# MCU.net
KiCad netlist of a schematic drawn in Altium Designer
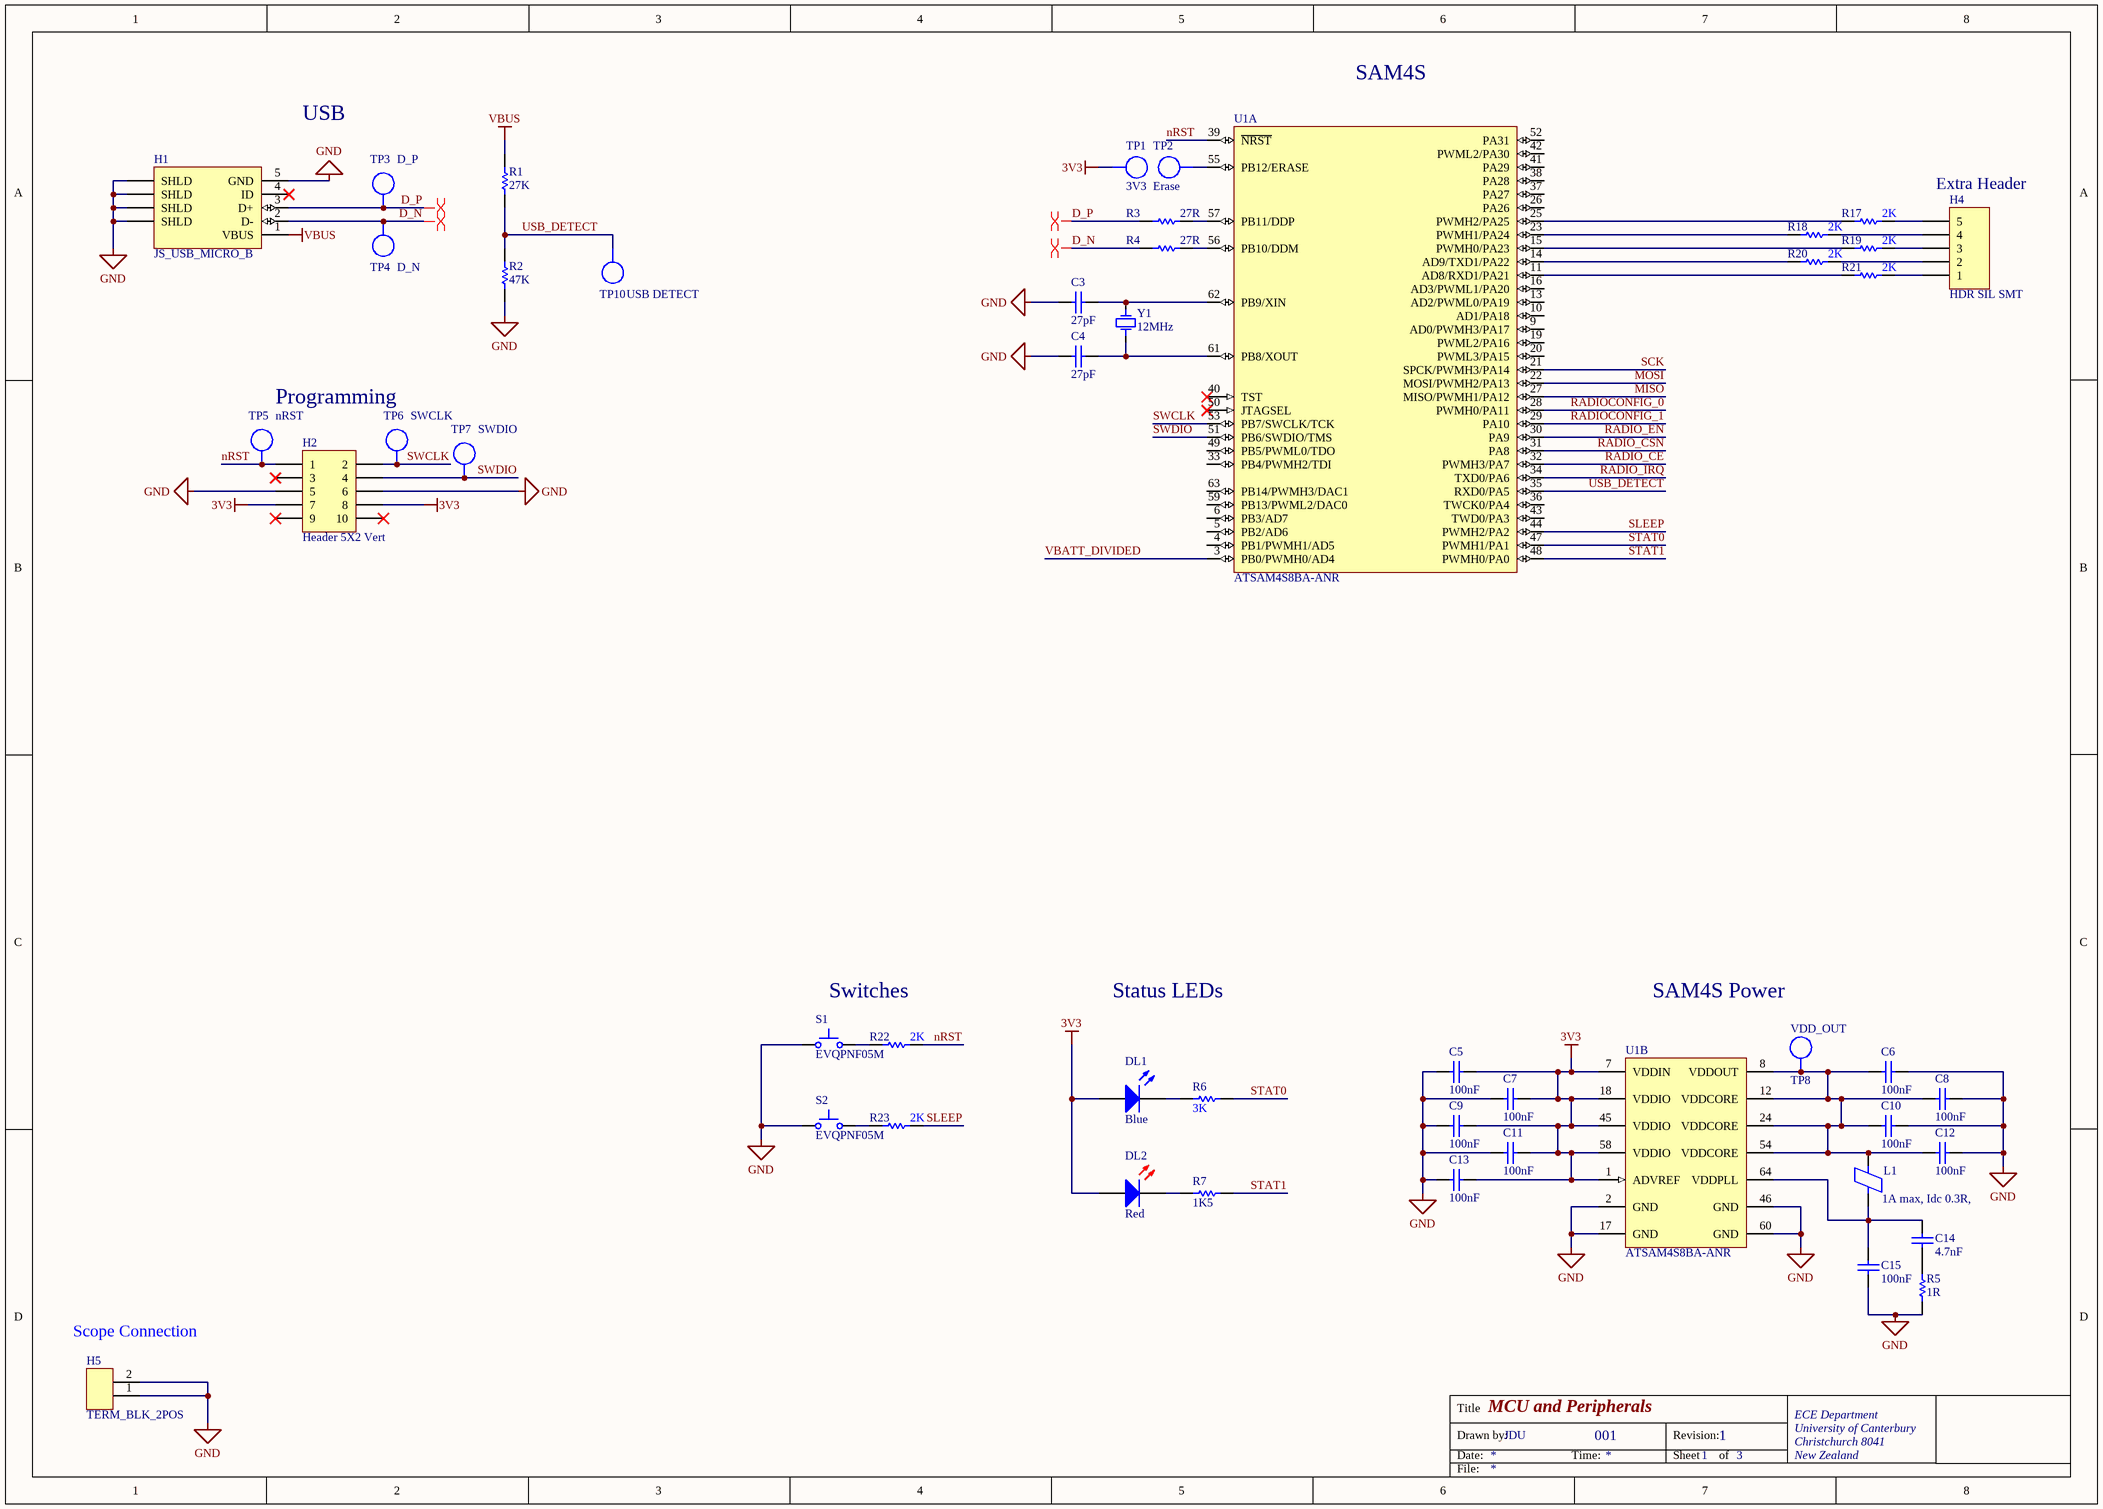
[diagram p0: MCU.SchDoc]

(export (version "E")
  (design (tool "Eeschema 10.0.6"))
  (components
    (comp (ref "C3")
      (value "27pF")
      (footprint "CAPC1608L")
      (description "CAP CER 27pF NPO/COG +-5% 50V 0603")
      (libsource (lib "ECE_ComponentsAD23") (part "CC_27pF_0603"))
    )
    (comp (ref "C4")
      (value "27pF")
      (footprint "CAPC1608L")
      (description "CAP CER 27pF NPO/COG +-5% 50V 0603")
      (libsource (lib "ECE_ComponentsAD23") (part "CC_27pF_0603"))
    )
    (comp (ref "C5")
      (value "100nF")
      (footprint "CAPC1608L")
      (description "CAP CER 100nF X7R +-10% 50V 0603")
      (libsource (lib "ECE_ComponentsAD23") (part "CC_100nF_0603"))
    )
    (comp (ref "C6")
      (value "100nF")
      (footprint "CAPC1608L")
      (description "CAP CER 100nF X7R +-10% 50V 0603")
      (libsource (lib "ECE_ComponentsAD23") (part "CC_100nF_0603"))
    )
    (comp (ref "C7")
      (value "100nF")
      (footprint "CAPC1608L")
      (description "CAP CER 100nF X7R +-10% 50V 0603")
      (libsource (lib "ECE_ComponentsAD23") (part "CC_100nF_0603"))
    )
    (comp (ref "C8")
      (value "100nF")
      (footprint "CAPC1608L")
      (description "CAP CER 100nF X7R +-10% 50V 0603")
      (libsource (lib "ECE_ComponentsAD23") (part "CC_100nF_0603"))
    )
    (comp (ref "C9")
      (value "100nF")
      (footprint "CAPC1608L")
      (description "CAP CER 100nF X7R +-10% 50V 0603")
      (libsource (lib "ECE_ComponentsAD23") (part "CC_100nF_0603"))
    )
    (comp (ref "C10")
      (value "100nF")
      (footprint "CAPC1608L")
      (description "CAP CER 100nF X7R +-10% 50V 0603")
      (libsource (lib "ECE_ComponentsAD23") (part "CC_100nF_0603"))
    )
    (comp (ref "C11")
      (value "100nF")
      (footprint "CAPC1608L")
      (description "CAP CER 100nF X7R +-10% 50V 0603")
      (libsource (lib "ECE_ComponentsAD23") (part "CC_100nF_0603"))
    )
    (comp (ref "C12")
      (value "100nF")
      (footprint "CAPC1608L")
      (description "CAP CER 100nF X7R +-10% 50V 0603")
      (libsource (lib "ECE_ComponentsAD23") (part "CC_100nF_0603"))
    )
    (comp (ref "C13")
      (value "100nF")
      (footprint "CAPC1608L")
      (description "CAP CER 100nF X7R +-10% 50V 0603")
      (libsource (lib "ECE_ComponentsAD23") (part "CC_100nF_0603"))
    )
    (comp (ref "C14")
      (value "4.7nF")
      (footprint "CAPC1608L")
      (description "CAP CER 4.7nF X7R +-10% 50V 0603")
      (libsource (lib "ECE_ComponentsAD23") (part "CC_4.7nF_0603"))
    )
    (comp (ref "C15")
      (value "100nF")
      (footprint "CAPC1608L")
      (description "CAP CER 100nF X7R +-10% 50V 0603")
      (libsource (lib "ECE_ComponentsAD23") (part "CC_100nF_0603"))
    )
    (comp (ref "DL1")
      (value "Blue")
      (footprint "WL-SMCW0603")
      (description "LED Blue 270mcd 0603 SMD")
      (fields
        (field (name "MANUFACTURER") "WURTH ELEKTRONIK")
        (field (name "MANUFACTURER PART NUMBER") "150060BS75000")
        (field (name "LED COLOUR") "Blue")
      )
      (libsource (lib "ECE_ComponentsAD23") (part "DL_150060BS75000"))
    )
    (comp (ref "DL2")
      (value "Red")
      (footprint "WL-SMCW0603")
      (description "LED Red 250mcd 0603 SMD")
      (fields
        (field (name "MANUFACTURER") "WURTH ELEKTRONIK")
        (field (name "MANUFACTURER PART NUMBER") "150060RS75000")
        (field (name "LED COLOUR") "Red")
      )
      (libsource (lib "ECE_ComponentsAD23") (part "DL_150060RS75000"))
    )
    (comp (ref "H1")
      (value "JS_USB_MICRO_B")
      (footprint "FCI_USB_10118194-0001LF")
      (description "CONN USB MICRO B RECPT SMT R/A")
      (fields (field (name "MANUFACTURER") "FCI") (field (name "MANUFACTURER PART NUMBER") "10118194-0001LF"))
      (libsource (lib "ECE_ComponentsAD23") (part "JS_USB_MICRO_B_SMT"))
    )
    (comp (ref "H2")
      (value "Header 5X2 Vert")
      (footprint "IDC2.54-V10D")
      (description "IDC Header, 2,54mm, 10-Pin, Vert")
      (libsource (lib "ECE_ComponentsAD23") (part "JA_HDR_IDC_5X2_VERT"))
    )
    (comp (ref "H4")
      (value "HDR SIL SMT")
      (footprint "M52-040000P0545")
      (description "Header 1.27mm Pitch SIL 5 Way SMT")
      (fields
        (field (name "MANUFACTURER") "HARWIN")
        (field (name "MANUFACTURER PART NUMBER") "M52-040000P0545")
      )
      (libsource (lib "ECE_ComponentsAD23") (part "JB_M52H_5_1.27"))
    )
    (comp (ref "H5")
      (value "TERM_BLK_2POS")
      (footprint "TERM_BLK_2POS")
      (description "2 Position Terminal Block 7.62mm spacing")
      (libsource (lib "ENCE461AD23") (part "TERM_BLK_2POS"))
    )
    (comp (ref "L1")
      (value "1A max, Idc 0.3R,")
      (footprint "INDC3216L")
      (description "Ferrite Bead, Rdc 0.3R, Z100MHZ 600R, Imax 1A, SMD 1206")
      (fields
        (field (name "MANUFACTURER") "FAIR-RITE")
        (field (name "MANUFACTURER PART NUMBER") "2512066017Y1")
      )
      (libsource (lib "ECE_ComponentsAD23") (part "IN_Ferrite-Bead"))
    )
    (comp (ref "R1")
      (value "27K")
      (footprint "RESC1608L")
      (description "RES 27K OHM 1/10W 5% 0603 SMD")
      (libsource (lib "ECE_ComponentsAD23") (part "RS_27K"))
    )
    (comp (ref "R2")
      (value "47K")
      (footprint "RESC1608N")
      (description "RES 47.0K OHM 1/10W 5% 0603 SMD")
      (libsource (lib "ECE_ComponentsAD23") (part "RS_47K"))
    )
    (comp (ref "R3")
      (value "27R")
      (footprint "RESC1608L")
      (description "RES 27 OHM 1/10W 5% 0603 SMD")
      (libsource (lib "ECE_ComponentsAD23") (part "RS_27R"))
    )
    (comp (ref "R4")
      (value "27R")
      (footprint "RESC1608L")
      (description "RES 27 OHM 1/10W 5% 0603 SMD")
      (libsource (lib "ECE_ComponentsAD23") (part "RS_27R"))
    )
    (comp (ref "R5")
      (value "1R")
      (footprint "RESC3216L")
      (description "RES 1R OHM 1/4W 5% 1206 SMD")
      (libsource (lib "ECE_ComponentsAD23") (part "RT_1R"))
    )
    (comp (ref "R6")
      (value "3K")
      (footprint "RESC1608L")
      (description "RES 3K OHM 1/10W 5% 0603 SMD")
      (libsource (lib "ECE_ComponentsAD23") (part "RS_3K"))
    )
    (comp (ref "R7")
      (value "1K5")
      (footprint "RESC1608L")
      (description "RES 1.5K OHM 1/10W 5% 0603 SMD")
      (libsource (lib "ECE_ComponentsAD23") (part "RS_1K5"))
    )
    (comp (ref "R17")
      (value "2K")
      (footprint "RESC1608L")
      (description "RES 2K OHM 1/10W 5% 0603 SMD")
      (libsource (lib "ECE_ComponentsAD23") (part "RS_2K"))
    )
    (comp (ref "R18")
      (value "2K")
      (footprint "RESC1608L")
      (description "RES 2K OHM 1/10W 5% 0603 SMD")
      (libsource (lib "ECE_ComponentsAD23") (part "RS_2K"))
    )
    (comp (ref "R19")
      (value "2K")
      (footprint "RESC1608L")
      (description "RES 2K OHM 1/10W 5% 0603 SMD")
      (libsource (lib "ECE_ComponentsAD23") (part "RS_2K"))
    )
    (comp (ref "R20")
      (value "2K")
      (footprint "RESC1608L")
      (description "RES 2K OHM 1/10W 5% 0603 SMD")
      (libsource (lib "ECE_ComponentsAD23") (part "RS_2K"))
    )
    (comp (ref "R21")
      (value "2K")
      (footprint "RESC1608L")
      (description "RES 2K OHM 1/10W 5% 0603 SMD")
      (libsource (lib "ECE_ComponentsAD23") (part "RS_2K"))
    )
    (comp (ref "R22")
      (value "2K")
      (footprint "RESC1608L")
      (description "RES 2K OHM 1/10W 5% 0603 SMD")
      (libsource (lib "ECE_ComponentsAD23") (part "RS_2K"))
    )
    (comp (ref "R23")
      (value "2K")
      (footprint "RESC1608L")
      (description "RES 2K OHM 1/10W 5% 0603 SMD")
      (libsource (lib "ECE_ComponentsAD23") (part "RS_2K"))
    )
    (comp (ref "S1")
      (value "EVQPNF05M")
      (footprint "EVQPNF05M")
      (description "Panasonic 6 x 3.5mm SMD Light Touch Switch Type SMD")
      (fields (field (name "MANUFACTURER") "Panasonic"))
      (libsource (lib "ECE_ComponentsAD23") (part "WS_EVQPNF05M"))
    )
    (comp (ref "S2")
      (value "EVQPNF05M")
      (footprint "EVQPNF05M")
      (description "Panasonic 6 x 3.5mm SMD Light Touch Switch Type SMD")
      (fields (field (name "MANUFACTURER") "Panasonic"))
      (libsource (lib "ECE_ComponentsAD23") (part "WS_EVQPNF05M"))
    )
    (comp (ref "TP1")
      (value "3V3")
      (footprint "TP_1206")
      (description "Test-Point 3.3x1.6x2.1mm SMD")
      (fields
        (field (name "MANUFACTURER") "Harwin Inc")
        (field (name "MANUFACTURER PART NUMBER") "S1751-46R")
      )
      (libsource (lib "ECE_ComponentsAD23") (part "TP_1206"))
    )
    (comp (ref "TP2")
      (value "Erase")
      (footprint "TP_1206")
      (description "Test-Point 3.3x1.6x2.1mm SMD")
      (fields
        (field (name "MANUFACTURER") "Harwin Inc")
        (field (name "MANUFACTURER PART NUMBER") "S1751-46R")
      )
      (libsource (lib "ECE_ComponentsAD23") (part "TP_1206"))
    )
    (comp (ref "TP3")
      (value "D_P")
      (footprint "TP_1206")
      (description "Test-Point 3.3x1.6x2.1mm SMD")
      (fields
        (field (name "MANUFACTURER") "Harwin Inc")
        (field (name "MANUFACTURER PART NUMBER") "S1751-46R")
      )
      (libsource (lib "ECE_ComponentsAD23") (part "TP_1206"))
    )
    (comp (ref "TP4")
      (value "D_N")
      (footprint "TP_1206")
      (description "Test-Point 3.3x1.6x2.1mm SMD")
      (fields
        (field (name "MANUFACTURER") "Harwin Inc")
        (field (name "MANUFACTURER PART NUMBER") "S1751-46R")
      )
      (libsource (lib "ECE_ComponentsAD23") (part "TP_1206"))
    )
    (comp (ref "TP5")
      (value "nRST")
      (footprint "TP_1206")
      (description "Test-Point 3.3x1.6x2.1mm SMD")
      (fields
        (field (name "MANUFACTURER") "Harwin Inc")
        (field (name "MANUFACTURER PART NUMBER") "S1751-46R")
      )
      (libsource (lib "ECE_ComponentsAD23") (part "TP_1206"))
    )
    (comp (ref "TP6")
      (value "SWCLK")
      (footprint "TP_1206")
      (description "Test-Point 3.3x1.6x2.1mm SMD")
      (fields
        (field (name "MANUFACTURER") "Harwin Inc")
        (field (name "MANUFACTURER PART NUMBER") "S1751-46R")
      )
      (libsource (lib "ECE_ComponentsAD23") (part "TP_1206"))
    )
    (comp (ref "TP7")
      (value "SWDIO")
      (footprint "TP_1206")
      (description "Test-Point 3.3x1.6x2.1mm SMD")
      (fields
        (field (name "MANUFACTURER") "Harwin Inc")
        (field (name "MANUFACTURER PART NUMBER") "S1751-46R")
      )
      (libsource (lib "ECE_ComponentsAD23") (part "TP_1206"))
    )
    (comp (ref "TP8")
      (value "VDD_OUT")
      (footprint "TP_1206")
      (description "Test-Point 3.3x1.6x2.1mm SMD")
      (fields
        (field (name "MANUFACTURER") "Harwin Inc")
        (field (name "MANUFACTURER PART NUMBER") "S1751-46R")
      )
      (libsource (lib "ECE_ComponentsAD23") (part "TP_1206"))
    )
    (comp (ref "TP10")
      (value "USB DETECT")
      (footprint "TP_1206")
      (description "Test-Point 3.3x1.6x2.1mm SMD")
      (fields
        (field (name "MANUFACTURER") "Harwin Inc")
        (field (name "MANUFACTURER PART NUMBER") "S1751-46R")
      )
      (libsource (lib "ECE_ComponentsAD23") (part "TP_1206"))
    )
    (comp (ref "U1")
      (value "ATSAM4S8BA-ANR")
      (footprint "LQFP64_L")
      (description "IC MCU 32BIT 512KB FLASH 64LQFP")
      (fields (field (name "MANUFACTURER") "Atmel"))
      (libsource (lib "ECE_ComponentsAD23") (part "SE_ATSAM4S16BA-MU"))
    )
    (comp (ref "Y1")
      (value "12MHz")
      (footprint "6.0X3.5-4")
      (description "CRYSTAL 12MHZ 18PF 6X3.5mm SMD")
      (fields
        (field (name "MANUFACTURER") "CTS-Frequency Controls")
        (field (name "MANUFACTURER PART NUMBER") "406C35D12M00000")
        (field (name "FREQUENCY") "12MHz")
      )
      (libsource (lib "ECE_ComponentsAD23") (part "XT_CRYSTAL_12MHz_18pF"))
    )
  )
  (nets
    (net (code "1") (name "/D_N") (class "Default")
      (node (ref "H1") (pin "2") (pinfunction "D-_2") (pintype "bidirectional"))
      (node (ref "R4") (pin "1") (pinfunction "1_1") (pintype "passive"))
      (node (ref "TP4") (pin "1") (pinfunction "1_1") (pintype "passive"))
    )
    (net (code "2") (name "/D_P") (class "Default")
      (node (ref "H1") (pin "3") (pinfunction "D+_3") (pintype "bidirectional"))
      (node (ref "R3") (pin "1") (pinfunction "1_1") (pintype "passive"))
      (node (ref "TP3") (pin "1") (pinfunction "1_1") (pintype "passive"))
    )
    (net (code "3") (name "/MISO") (class "Default")
      (node (ref "U1") (pin "27") (pinfunction "MISO/PWMH1/PA12_27") (pintype "bidirectional"))
    )
    (net (code "4") (name "/MOSI") (class "Default")
      (node (ref "U1") (pin "22") (pinfunction "MOSI/PWMH2/PA13_22") (pintype "bidirectional"))
    )
    (net (code "5") (name "/RADIOCONFIG_0") (class "Default")
      (node (ref "U1") (pin "28") (pinfunction "PWMH0/PA11_28") (pintype "bidirectional"))
    )
    (net (code "6") (name "/RADIOCONFIG_1") (class "Default")
      (node (ref "U1") (pin "29") (pinfunction "PA10_29") (pintype "bidirectional"))
    )
    (net (code "7") (name "/RADIO_CE") (class "Default")
      (node (ref "U1") (pin "32") (pinfunction "PWMH3/PA7_32") (pintype "bidirectional"))
    )
    (net (code "8") (name "/RADIO_CSN") (class "Default")
      (node (ref "U1") (pin "31") (pinfunction "PA8_31") (pintype "bidirectional"))
    )
    (net (code "9") (name "/RADIO_EN") (class "Default")
      (node (ref "U1") (pin "30") (pinfunction "PA9_30") (pintype "bidirectional"))
    )
    (net (code "10") (name "/RADIO_IRQ") (class "Default")
      (node (ref "U1") (pin "34") (pinfunction "TXD0/PA6_34") (pintype "bidirectional"))
    )
    (net (code "11") (name "/SCK") (class "Default")
      (node (ref "U1") (pin "21") (pinfunction "SPCK/PWMH3/PA14_21") (pintype "bidirectional"))
    )
    (net (code "12") (name "/SLEEP") (class "Default")
      (node (ref "R23") (pin "2") (pinfunction "2_2") (pintype "passive"))
      (node (ref "U1") (pin "44") (pinfunction "PWMH2/PA2_44") (pintype "bidirectional"))
    )
    (net (code "13") (name "/STAT0") (class "Default")
      (node (ref "R6") (pin "2") (pinfunction "2_2") (pintype "passive"))
      (node (ref "U1") (pin "47") (pinfunction "PWMH1/PA1_47") (pintype "bidirectional"))
    )
    (net (code "14") (name "/STAT1") (class "Default")
      (node (ref "R7") (pin "2") (pinfunction "2_2") (pintype "passive"))
      (node (ref "U1") (pin "48") (pinfunction "PWMH0/PA0_48") (pintype "bidirectional"))
    )
    (net (code "15") (name "/SWCLK") (class "Default")
      (node (ref "H2") (pin "2") (pinfunction "2_2") (pintype "passive"))
      (node (ref "TP6") (pin "1") (pinfunction "1_1") (pintype "passive"))
      (node (ref "U1") (pin "53") (pinfunction "PB7/SWCLK/TCK_53") (pintype "bidirectional"))
    )
    (net (code "16") (name "/SWDIO") (class "Default")
      (node (ref "H2") (pin "4") (pinfunction "4_4") (pintype "passive"))
      (node (ref "TP7") (pin "1") (pinfunction "1_1") (pintype "passive"))
      (node (ref "U1") (pin "51") (pinfunction "PB6/SWDIO/TMS_51") (pintype "bidirectional"))
    )
    (net (code "17") (name "/USB_DETECT") (class "Default")
      (node (ref "R1") (pin "1") (pinfunction "1_1") (pintype "passive"))
      (node (ref "R2") (pin "2") (pinfunction "2_2") (pintype "passive"))
      (node (ref "TP10") (pin "1") (pinfunction "1_1") (pintype "passive"))
      (node (ref "U1") (pin "35") (pinfunction "RXD0/PA5_35") (pintype "bidirectional"))
    )
    (net (code "18") (name "/VBATT_DIVIDED") (class "Default")
      (node (ref "U1") (pin "3") (pinfunction "PB0/PWMH0/AD4_3") (pintype "bidirectional"))
    )
    (net (code "19") (name "/nRST") (class "Default")
      (node (ref "H2") (pin "1") (pinfunction "1_1") (pintype "passive"))
      (node (ref "R22") (pin "2") (pinfunction "2_2") (pintype "passive"))
      (node (ref "TP5") (pin "1") (pinfunction "1_1") (pintype "passive"))
      (node (ref "U1") (pin "39") (pinfunction "~{NRST}_39") (pintype "bidirectional"))
    )
    (net (code "20") (name "3V3") (class "Default")
      (node (ref "C11") (pin "2") (pinfunction "2_2") (pintype "passive"))
      (node (ref "C13") (pin "2") (pinfunction "2_2") (pintype "passive"))
      (node (ref "C5") (pin "2") (pinfunction "2_2") (pintype "passive"))
      (node (ref "C7") (pin "2") (pinfunction "2_2") (pintype "passive"))
      (node (ref "C9") (pin "2") (pinfunction "2_2") (pintype "passive"))
      (node (ref "DL1") (pin "2") (pinfunction "A_2") (pintype "passive"))
      (node (ref "DL2") (pin "2") (pinfunction "A_2") (pintype "passive"))
      (node (ref "H2") (pin "7") (pinfunction "7_7") (pintype "passive"))
      (node (ref "H2") (pin "8") (pinfunction "8_8") (pintype "passive"))
      (node (ref "TP1") (pin "1") (pinfunction "1_1") (pintype "passive"))
      (node (ref "U1") (pin "1") (pinfunction "ADVREF_1") (pintype "input"))
      (node (ref "U1") (pin "18") (pinfunction "VDDIO_18") (pintype "power_in"))
      (node (ref "U1") (pin "45") (pinfunction "VDDIO_45") (pintype "power_in"))
      (node (ref "U1") (pin "58") (pinfunction "VDDIO_58") (pintype "power_in"))
      (node (ref "U1") (pin "7") (pinfunction "VDDIN_7") (pintype "power_in"))
    )
    (net (code "21") (name "GND") (class "Default")
      (node (ref "C10") (pin "2") (pinfunction "2_2") (pintype "passive"))
      (node (ref "C11") (pin "1") (pinfunction "1_1") (pintype "passive"))
      (node (ref "C12") (pin "2") (pinfunction "2_2") (pintype "passive"))
      (node (ref "C13") (pin "1") (pinfunction "1_1") (pintype "passive"))
      (node (ref "C15") (pin "1") (pinfunction "1_1") (pintype "passive"))
      (node (ref "C3") (pin "1") (pinfunction "1_1") (pintype "passive"))
      (node (ref "C4") (pin "1") (pinfunction "1_1") (pintype "passive"))
      (node (ref "C5") (pin "1") (pinfunction "1_1") (pintype "passive"))
      (node (ref "C6") (pin "2") (pinfunction "2_2") (pintype "passive"))
      (node (ref "C7") (pin "1") (pinfunction "1_1") (pintype "passive"))
      (node (ref "C8") (pin "2") (pinfunction "2_2") (pintype "passive"))
      (node (ref "C9") (pin "1") (pinfunction "1_1") (pintype "passive"))
      (node (ref "H1") (pin "5") (pinfunction "GND_5") (pintype "passive"))
      (node (ref "H1") (pin "6") (pinfunction "SHLD_6") (pintype "passive"))
      (node (ref "H2") (pin "5") (pinfunction "5_5") (pintype "passive"))
      (node (ref "H2") (pin "6") (pinfunction "6_6") (pintype "passive"))
      (node (ref "H5") (pin "1") (pintype "passive"))
      (node (ref "H5") (pin "2") (pintype "passive"))
      (node (ref "R2") (pin "1") (pinfunction "1_1") (pintype "passive"))
      (node (ref "R5") (pin "1") (pinfunction "1_1") (pintype "passive"))
      (node (ref "S1") (pin "1") (pintype "passive"))
      (node (ref "S2") (pin "1") (pintype "passive"))
      (node (ref "U1") (pin "17") (pinfunction "GND_17") (pintype "power_in"))
      (node (ref "U1") (pin "2") (pinfunction "GND_2") (pintype "power_in"))
      (node (ref "U1") (pin "46") (pinfunction "GND_46") (pintype "power_in"))
      (node (ref "U1") (pin "60") (pinfunction "GND_60") (pintype "power_in"))
    )
    (net (code "22") (name "Net-(C14-Pad1)") (class "Default")
      (node (ref "C14") (pin "1") (pinfunction "1_1") (pintype "passive"))
      (node (ref "R5") (pin "2") (pinfunction "2_2") (pintype "passive"))
    )
    (net (code "23") (name "Net-(DL1-K)") (class "Default")
      (node (ref "DL1") (pin "1") (pinfunction "K_1") (pintype "passive"))
      (node (ref "R6") (pin "1") (pinfunction "1_1") (pintype "passive"))
    )
    (net (code "24") (name "Net-(DL2-K)") (class "Default")
      (node (ref "DL2") (pin "1") (pinfunction "K_1") (pintype "passive"))
      (node (ref "R7") (pin "1") (pinfunction "1_1") (pintype "passive"))
    )
    (net (code "25") (name "Net-(H4-Pad1)") (class "Default")
      (node (ref "H4") (pin "1") (pinfunction "1_1") (pintype "passive"))
      (node (ref "R21") (pin "2") (pinfunction "2_2") (pintype "passive"))
    )
    (net (code "26") (name "Net-(H4-Pad2)") (class "Default")
      (node (ref "H4") (pin "2") (pinfunction "2_2") (pintype "passive"))
      (node (ref "R20") (pin "2") (pinfunction "2_2") (pintype "passive"))
    )
    (net (code "27") (name "Net-(H4-Pad3)") (class "Default")
      (node (ref "H4") (pin "3") (pinfunction "3_3") (pintype "passive"))
      (node (ref "R19") (pin "2") (pinfunction "2_2") (pintype "passive"))
    )
    (net (code "28") (name "Net-(H4-Pad4)") (class "Default")
      (node (ref "H4") (pin "4") (pinfunction "4_4") (pintype "passive"))
      (node (ref "R18") (pin "2") (pinfunction "2_2") (pintype "passive"))
    )
    (net (code "29") (name "Net-(H4-Pad5)") (class "Default")
      (node (ref "H4") (pin "5") (pinfunction "5_5") (pintype "passive"))
      (node (ref "R17") (pin "2") (pinfunction "2_2") (pintype "passive"))
    )
    (net (code "30") (name "Net-(R22-Pad1)") (class "Default")
      (node (ref "R22") (pin "1") (pinfunction "1_1") (pintype "passive"))
      (node (ref "S1") (pin "2") (pintype "passive"))
    )
    (net (code "31") (name "Net-(R23-Pad1)") (class "Default")
      (node (ref "R23") (pin "1") (pinfunction "1_1") (pintype "passive"))
      (node (ref "S2") (pin "2") (pintype "passive"))
    )
    (net (code "32") (name "Net-(U1A-AD8{slash}RXD1{slash}PA21)") (class "Default")
      (node (ref "R21") (pin "1") (pinfunction "1_1") (pintype "passive"))
      (node (ref "U1") (pin "11") (pinfunction "AD8/RXD1/PA21_11") (pintype "bidirectional"))
    )
    (net (code "33") (name "Net-(U1A-AD9{slash}TXD1{slash}PA22)") (class "Default")
      (node (ref "R20") (pin "1") (pinfunction "1_1") (pintype "passive"))
      (node (ref "U1") (pin "14") (pinfunction "AD9/TXD1/PA22_14") (pintype "bidirectional"))
    )
    (net (code "34") (name "Net-(U1A-PB8{slash}XOUT)") (class "Default")
      (node (ref "C4") (pin "2") (pinfunction "2_2") (pintype "passive"))
      (node (ref "U1") (pin "61") (pinfunction "PB8/XOUT_61") (pintype "bidirectional"))
      (node (ref "Y1") (pin "1") (pinfunction "OSC1_1") (pintype "passive"))
    )
    (net (code "35") (name "Net-(U1A-PB9{slash}XIN)") (class "Default")
      (node (ref "C3") (pin "2") (pinfunction "2_2") (pintype "passive"))
      (node (ref "U1") (pin "62") (pinfunction "PB9/XIN_62") (pintype "bidirectional"))
      (node (ref "Y1") (pin "3") (pinfunction "OSC2_3") (pintype "passive"))
    )
    (net (code "36") (name "Net-(U1A-PB10{slash}DDM)") (class "Default")
      (node (ref "R4") (pin "2") (pinfunction "2_2") (pintype "passive"))
      (node (ref "U1") (pin "56") (pinfunction "PB10/DDM_56") (pintype "bidirectional"))
    )
    (net (code "37") (name "Net-(U1A-PB11{slash}DDP)") (class "Default")
      (node (ref "R3") (pin "2") (pinfunction "2_2") (pintype "passive"))
      (node (ref "U1") (pin "57") (pinfunction "PB11/DDP_57") (pintype "bidirectional"))
    )
    (net (code "38") (name "Net-(U1A-PB12{slash}ERASE)") (class "Default")
      (node (ref "TP2") (pin "1") (pinfunction "1_1") (pintype "passive"))
      (node (ref "U1") (pin "55") (pinfunction "PB12/ERASE_55") (pintype "bidirectional"))
    )
    (net (code "39") (name "Net-(U1A-PWMH0{slash}PA23)") (class "Default")
      (node (ref "R19") (pin "1") (pinfunction "1_1") (pintype "passive"))
      (node (ref "U1") (pin "15") (pinfunction "PWMH0/PA23_15") (pintype "bidirectional"))
    )
    (net (code "40") (name "Net-(U1A-PWMH1{slash}PA24)") (class "Default")
      (node (ref "R18") (pin "1") (pinfunction "1_1") (pintype "passive"))
      (node (ref "U1") (pin "23") (pinfunction "PWMH1/PA24_23") (pintype "bidirectional"))
    )
    (net (code "41") (name "Net-(U1A-PWMH2{slash}PA25)") (class "Default")
      (node (ref "R17") (pin "1") (pinfunction "1_1") (pintype "passive"))
      (node (ref "U1") (pin "25") (pinfunction "PWMH2/PA25_25") (pintype "bidirectional"))
    )
    (net (code "42") (name "Net-(U1B-VDDOUT)") (class "Default")
      (node (ref "C10") (pin "1") (pinfunction "1_1") (pintype "passive"))
      (node (ref "C12") (pin "1") (pinfunction "1_1") (pintype "passive"))
      (node (ref "C6") (pin "1") (pinfunction "1_1") (pintype "passive"))
      (node (ref "C8") (pin "1") (pinfunction "1_1") (pintype "passive"))
      (node (ref "L1") (pin "2") (pinfunction "2_2") (pintype "passive"))
      (node (ref "TP8") (pin "1") (pinfunction "1_1") (pintype "passive"))
      (node (ref "U1") (pin "12") (pinfunction "VDDCORE_12") (pintype "power_in"))
      (node (ref "U1") (pin "24") (pinfunction "VDDCORE_24") (pintype "power_in"))
      (node (ref "U1") (pin "54") (pinfunction "VDDCORE_54") (pintype "power_in"))
      (node (ref "U1") (pin "8") (pinfunction "VDDOUT_8") (pintype "power_in"))
    )
    (net (code "43") (name "Net-(U1B-VDDPLL)") (class "Default")
      (node (ref "C14") (pin "2") (pinfunction "2_2") (pintype "passive"))
      (node (ref "C15") (pin "2") (pinfunction "2_2") (pintype "passive"))
      (node (ref "L1") (pin "1") (pinfunction "1_1") (pintype "passive"))
      (node (ref "U1") (pin "64") (pinfunction "VDDPLL_64") (pintype "power_in"))
    )
    (net (code "44") (name "VBUS") (class "Default")
      (node (ref "H1") (pin "1") (pinfunction "VBUS_1") (pintype "power_in"))
      (node (ref "R1") (pin "2") (pinfunction "2_2") (pintype "passive"))
    )
    (net (code "45") (name "unconnected-(H1-ID-Pad4)") (class "Default")
      (node (ref "H1") (pin "4") (pinfunction "ID_4") (pintype "power_in+no_connect"))
    )
    (net (code "46") (name "unconnected-(H2-Pad3)") (class "Default")
      (node (ref "H2") (pin "3") (pinfunction "3_3") (pintype "passive+no_connect"))
    )
    (net (code "47") (name "unconnected-(H2-Pad9)") (class "Default")
      (node (ref "H2") (pin "9") (pinfunction "9_9") (pintype "passive+no_connect"))
    )
    (net (code "48") (name "unconnected-(H2-Pad10)") (class "Default")
      (node (ref "H2") (pin "10") (pinfunction "10_10") (pintype "passive+no_connect"))
    )
    (net (code "49") (name "unconnected-(U1A-AD0{slash}PWMH3{slash}PA17-Pad9)") (class "Default")
      (node (ref "U1") (pin "9") (pinfunction "AD0/PWMH3/PA17_9") (pintype "bidirectional"))
    )
    (net (code "50") (name "unconnected-(U1A-AD1{slash}PA18-Pad10)") (class "Default")
      (node (ref "U1") (pin "10") (pinfunction "AD1/PA18_10") (pintype "bidirectional"))
    )
    (net (code "51") (name "unconnected-(U1A-AD2{slash}PWML0{slash}PA19-Pad13)") (class "Default")
      (node (ref "U1") (pin "13") (pinfunction "AD2/PWML0/PA19_13") (pintype "bidirectional"))
    )
    (net (code "52") (name "unconnected-(U1A-AD3{slash}PWML1{slash}PA20-Pad16)") (class "Default")
      (node (ref "U1") (pin "16") (pinfunction "AD3/PWML1/PA20_16") (pintype "bidirectional"))
    )
    (net (code "53") (name "unconnected-(U1A-JTAGSEL-Pad50)") (class "Default")
      (node (ref "U1") (pin "50") (pinfunction "JTAGSEL_50") (pintype "input+no_connect"))
    )
    (net (code "54") (name "unconnected-(U1A-PA26-Pad26)") (class "Default")
      (node (ref "U1") (pin "26") (pinfunction "PA26_26") (pintype "bidirectional"))
    )
    (net (code "55") (name "unconnected-(U1A-PA27-Pad37)") (class "Default")
      (node (ref "U1") (pin "37") (pinfunction "PA27_37") (pintype "bidirectional"))
    )
    (net (code "56") (name "unconnected-(U1A-PA28-Pad38)") (class "Default")
      (node (ref "U1") (pin "38") (pinfunction "PA28_38") (pintype "bidirectional"))
    )
    (net (code "57") (name "unconnected-(U1A-PA29-Pad41)") (class "Default")
      (node (ref "U1") (pin "41") (pinfunction "PA29_41") (pintype "bidirectional"))
    )
    (net (code "58") (name "unconnected-(U1A-PA31-Pad52)") (class "Default")
      (node (ref "U1") (pin "52") (pinfunction "PA31_52") (pintype "bidirectional"))
    )
    (net (code "59") (name "unconnected-(U1A-PB1{slash}PWMH1{slash}AD5-Pad4)") (class "Default")
      (node (ref "U1") (pin "4") (pinfunction "PB1/PWMH1/AD5_4") (pintype "bidirectional"))
    )
    (net (code "60") (name "unconnected-(U1A-PB2{slash}AD6-Pad5)") (class "Default")
      (node (ref "U1") (pin "5") (pinfunction "PB2/AD6_5") (pintype "bidirectional"))
    )
    (net (code "61") (name "unconnected-(U1A-PB3{slash}AD7-Pad6)") (class "Default")
      (node (ref "U1") (pin "6") (pinfunction "PB3/AD7_6") (pintype "bidirectional"))
    )
    (net (code "62") (name "unconnected-(U1A-PB4{slash}PWMH2{slash}TDI-Pad33)") (class "Default")
      (node (ref "U1") (pin "33") (pinfunction "PB4/PWMH2/TDI_33") (pintype "bidirectional"))
    )
    (net (code "63") (name "unconnected-(U1A-PB5{slash}PWML0{slash}TDO-Pad49)") (class "Default")
      (node (ref "U1") (pin "49") (pinfunction "PB5/PWML0/TDO_49") (pintype "bidirectional"))
    )
    (net (code "64") (name "unconnected-(U1A-PB13{slash}PWML2{slash}DAC0-Pad59)") (class "Default")
      (node (ref "U1") (pin "59") (pinfunction "PB13/PWML2/DAC0_59") (pintype "bidirectional"))
    )
    (net (code "65") (name "unconnected-(U1A-PB14{slash}PWMH3{slash}DAC1-Pad63)") (class "Default")
      (node (ref "U1") (pin "63") (pinfunction "PB14/PWMH3/DAC1_63") (pintype "bidirectional"))
    )
    (net (code "66") (name "unconnected-(U1A-PWML2{slash}PA16-Pad19)") (class "Default")
      (node (ref "U1") (pin "19") (pinfunction "PWML2/PA16_19") (pintype "bidirectional"))
    )
    (net (code "67") (name "unconnected-(U1A-PWML2{slash}PA30-Pad42)") (class "Default")
      (node (ref "U1") (pin "42") (pinfunction "PWML2/PA30_42") (pintype "bidirectional"))
    )
    (net (code "68") (name "unconnected-(U1A-PWML3{slash}PA15-Pad20)") (class "Default")
      (node (ref "U1") (pin "20") (pinfunction "PWML3/PA15_20") (pintype "bidirectional"))
    )
    (net (code "69") (name "unconnected-(U1A-TST-Pad40)") (class "Default")
      (node (ref "U1") (pin "40") (pinfunction "TST_40") (pintype "input+no_connect"))
    )
    (net (code "70") (name "unconnected-(U1A-TWCK0{slash}PA4-Pad36)") (class "Default")
      (node (ref "U1") (pin "36") (pinfunction "TWCK0/PA4_36") (pintype "bidirectional"))
    )
    (net (code "71") (name "unconnected-(U1A-TWD0{slash}PA3-Pad43)") (class "Default")
      (node (ref "U1") (pin "43") (pinfunction "TWD0/PA3_43") (pintype "bidirectional"))
    )
  )
)
